# keeboartouch.net
KiCad netlist of a schematic drawn in EAGLE
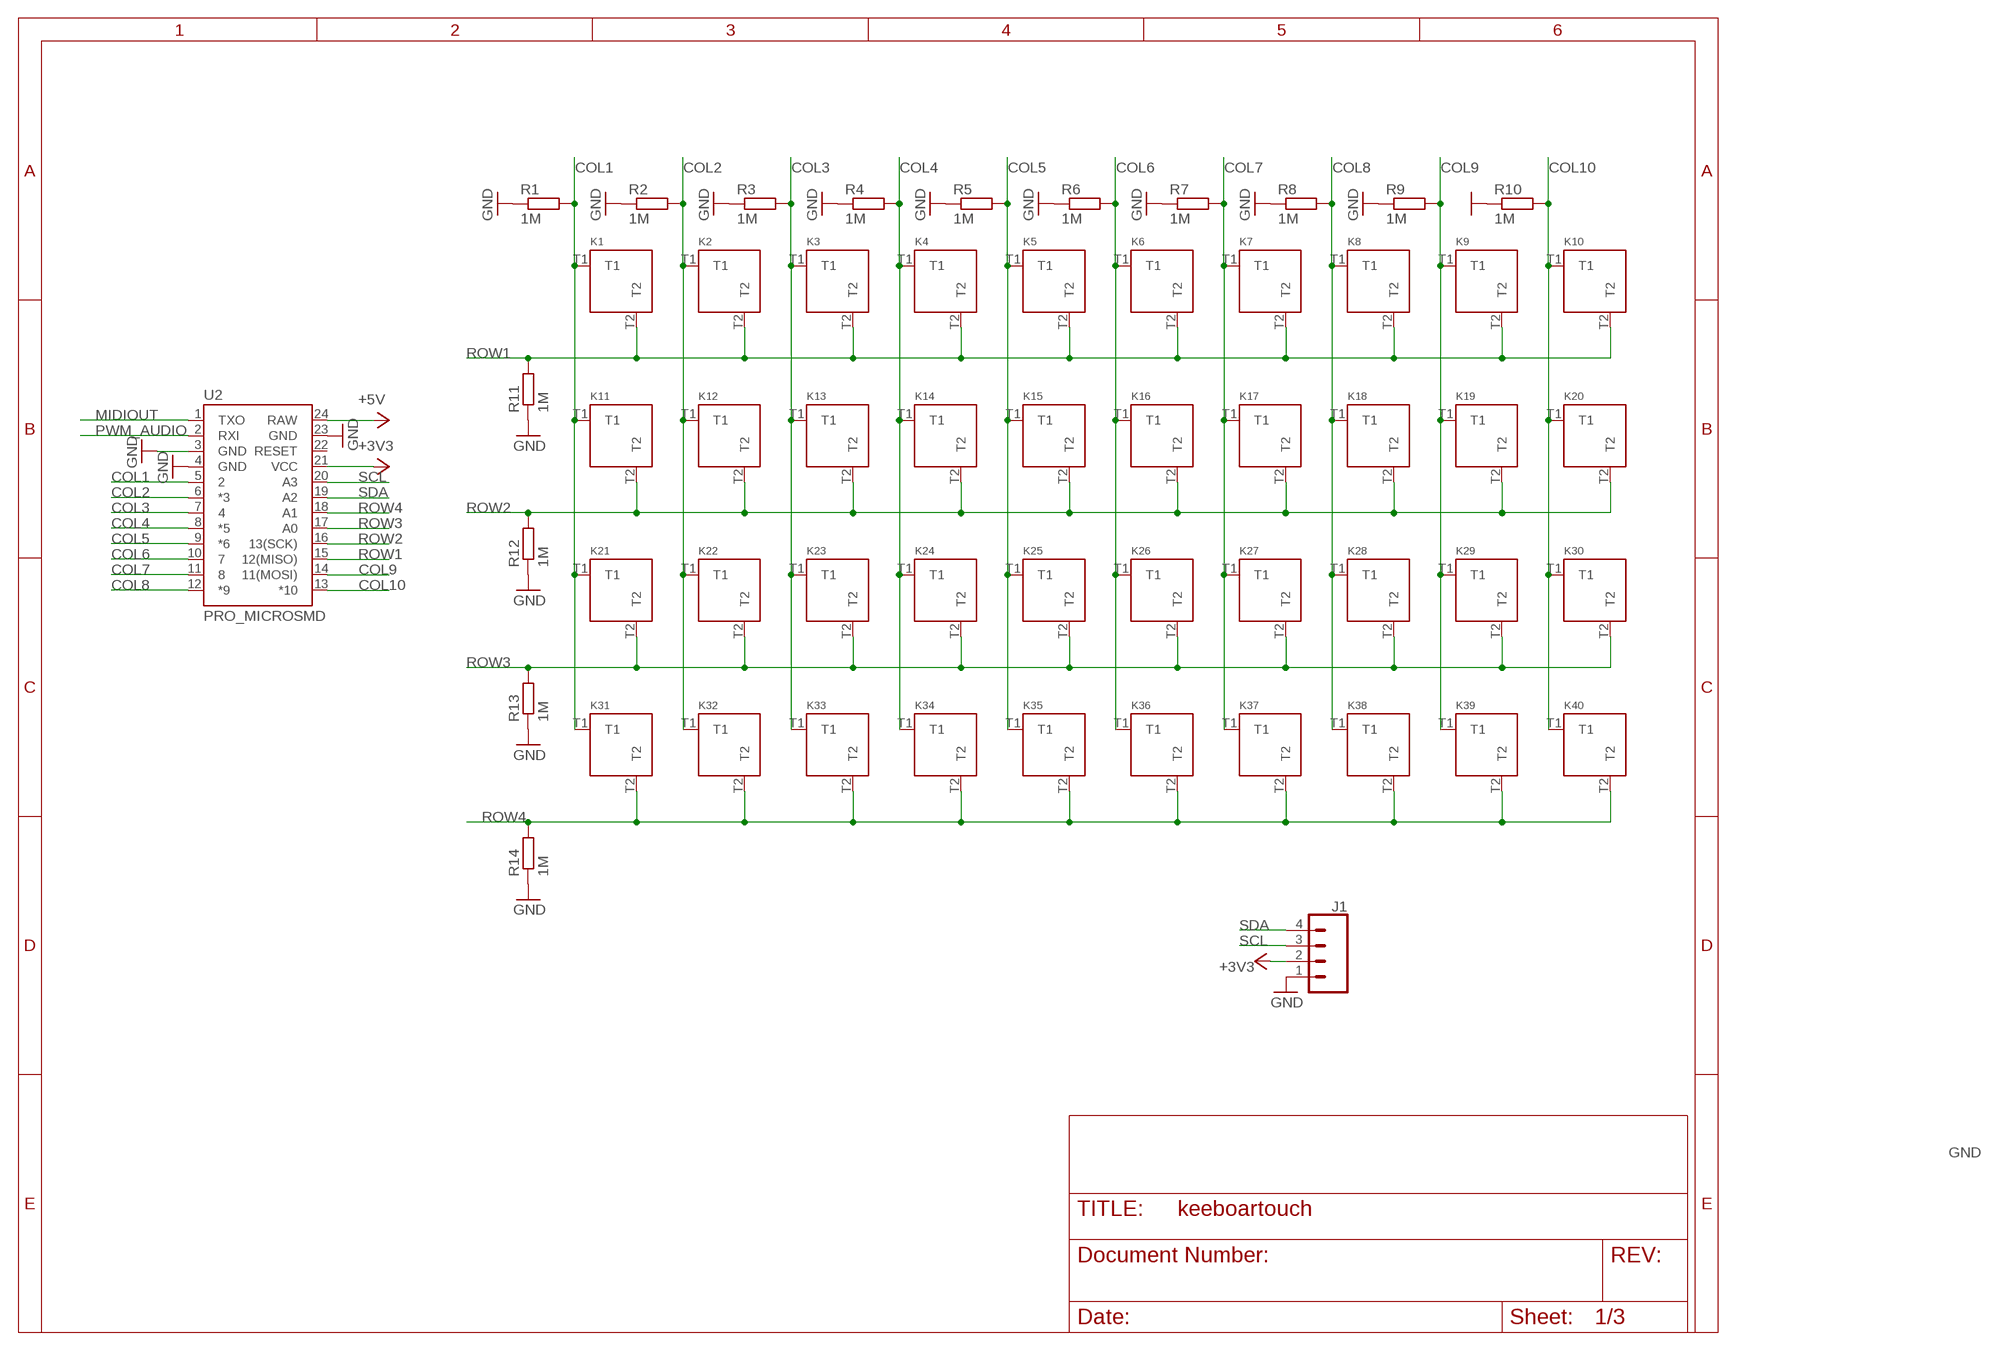
[diagram p0: schematic, sheet 1]

(export (version "E")
  (design (tool "Eeschema 10.0.6"))
  (components
    (comp (ref "J1")
      (value "CONN_04")
      (footprint "eagle-import:1X04")
      (libsource (lib "eagle-import") (part "CONN_04"))
    )
    (comp (ref "K1")
      (value "TOUCHKEY")
      (footprint "eagle-import:TOUCHPAD_KEY_0.5IN")
      (libsource (lib "eagle-import") (part "TOUCHKEY"))
    )
    (comp (ref "K2")
      (value "TOUCHKEY")
      (footprint "eagle-import:TOUCHPAD_KEY_0.5IN")
      (libsource (lib "eagle-import") (part "TOUCHKEY"))
    )
    (comp (ref "K3")
      (value "TOUCHKEY")
      (footprint "eagle-import:TOUCHPAD_KEY_0.5IN")
      (libsource (lib "eagle-import") (part "TOUCHKEY"))
    )
    (comp (ref "K4")
      (value "TOUCHKEY")
      (footprint "eagle-import:TOUCHPAD_KEY_0.5IN")
      (libsource (lib "eagle-import") (part "TOUCHKEY"))
    )
    (comp (ref "K5")
      (value "TOUCHKEY")
      (footprint "eagle-import:TOUCHPAD_KEY_0.5IN")
      (libsource (lib "eagle-import") (part "TOUCHKEY"))
    )
    (comp (ref "K6")
      (value "TOUCHKEY")
      (footprint "eagle-import:TOUCHPAD_KEY_0.5IN")
      (libsource (lib "eagle-import") (part "TOUCHKEY"))
    )
    (comp (ref "K7")
      (value "TOUCHKEY")
      (footprint "eagle-import:TOUCHPAD_KEY_0.5IN")
      (libsource (lib "eagle-import") (part "TOUCHKEY"))
    )
    (comp (ref "K8")
      (value "TOUCHKEY")
      (footprint "eagle-import:TOUCHPAD_KEY_0.5IN")
      (libsource (lib "eagle-import") (part "TOUCHKEY"))
    )
    (comp (ref "K9")
      (value "TOUCHKEY")
      (footprint "eagle-import:TOUCHPAD_KEY_0.5IN")
      (libsource (lib "eagle-import") (part "TOUCHKEY"))
    )
    (comp (ref "K10")
      (value "TOUCHKEY")
      (footprint "eagle-import:TOUCHPAD_KEY_0.5IN")
      (libsource (lib "eagle-import") (part "TOUCHKEY"))
    )
    (comp (ref "K11")
      (value "TOUCHKEY")
      (footprint "eagle-import:TOUCHPAD_KEY_0.5IN")
      (libsource (lib "eagle-import") (part "TOUCHKEY"))
    )
    (comp (ref "K12")
      (value "TOUCHKEY")
      (footprint "eagle-import:TOUCHPAD_KEY_0.5IN")
      (libsource (lib "eagle-import") (part "TOUCHKEY"))
    )
    (comp (ref "K13")
      (value "TOUCHKEY")
      (footprint "eagle-import:TOUCHPAD_KEY_0.5IN")
      (libsource (lib "eagle-import") (part "TOUCHKEY"))
    )
    (comp (ref "K14")
      (value "TOUCHKEY")
      (footprint "eagle-import:TOUCHPAD_KEY_0.5IN")
      (libsource (lib "eagle-import") (part "TOUCHKEY"))
    )
    (comp (ref "K15")
      (value "TOUCHKEY")
      (footprint "eagle-import:TOUCHPAD_KEY_0.5IN")
      (libsource (lib "eagle-import") (part "TOUCHKEY"))
    )
    (comp (ref "K16")
      (value "TOUCHKEY")
      (footprint "eagle-import:TOUCHPAD_KEY_0.5IN")
      (libsource (lib "eagle-import") (part "TOUCHKEY"))
    )
    (comp (ref "K17")
      (value "TOUCHKEY")
      (footprint "eagle-import:TOUCHPAD_KEY_0.5IN")
      (libsource (lib "eagle-import") (part "TOUCHKEY"))
    )
    (comp (ref "K18")
      (value "TOUCHKEY")
      (footprint "eagle-import:TOUCHPAD_KEY_0.5IN")
      (libsource (lib "eagle-import") (part "TOUCHKEY"))
    )
    (comp (ref "K19")
      (value "TOUCHKEY")
      (footprint "eagle-import:TOUCHPAD_KEY_0.5IN")
      (libsource (lib "eagle-import") (part "TOUCHKEY"))
    )
    (comp (ref "K20")
      (value "TOUCHKEY")
      (footprint "eagle-import:TOUCHPAD_KEY_0.5IN")
      (libsource (lib "eagle-import") (part "TOUCHKEY"))
    )
    (comp (ref "K21")
      (value "TOUCHKEY")
      (footprint "eagle-import:TOUCHPAD_KEY_0.5IN")
      (libsource (lib "eagle-import") (part "TOUCHKEY"))
    )
    (comp (ref "K22")
      (value "TOUCHKEY")
      (footprint "eagle-import:TOUCHPAD_KEY_0.5IN")
      (libsource (lib "eagle-import") (part "TOUCHKEY"))
    )
    (comp (ref "K23")
      (value "TOUCHKEY")
      (footprint "eagle-import:TOUCHPAD_KEY_0.5IN")
      (libsource (lib "eagle-import") (part "TOUCHKEY"))
    )
    (comp (ref "K24")
      (value "TOUCHKEY")
      (footprint "eagle-import:TOUCHPAD_KEY_0.5IN")
      (libsource (lib "eagle-import") (part "TOUCHKEY"))
    )
    (comp (ref "K25")
      (value "TOUCHKEY")
      (footprint "eagle-import:TOUCHPAD_KEY_0.5IN")
      (libsource (lib "eagle-import") (part "TOUCHKEY"))
    )
    (comp (ref "K26")
      (value "TOUCHKEY")
      (footprint "eagle-import:TOUCHPAD_KEY_0.5IN")
      (libsource (lib "eagle-import") (part "TOUCHKEY"))
    )
    (comp (ref "K27")
      (value "TOUCHKEY")
      (footprint "eagle-import:TOUCHPAD_KEY_0.5IN")
      (libsource (lib "eagle-import") (part "TOUCHKEY"))
    )
    (comp (ref "K28")
      (value "TOUCHKEY")
      (footprint "eagle-import:TOUCHPAD_KEY_0.5IN")
      (libsource (lib "eagle-import") (part "TOUCHKEY"))
    )
    (comp (ref "K29")
      (value "TOUCHKEY")
      (footprint "eagle-import:TOUCHPAD_KEY_0.5IN")
      (libsource (lib "eagle-import") (part "TOUCHKEY"))
    )
    (comp (ref "K30")
      (value "TOUCHKEY")
      (footprint "eagle-import:TOUCHPAD_KEY_0.5IN")
      (libsource (lib "eagle-import") (part "TOUCHKEY"))
    )
    (comp (ref "K31")
      (value "TOUCHKEY")
      (footprint "eagle-import:TOUCHPAD_KEY_0.5IN")
      (libsource (lib "eagle-import") (part "TOUCHKEY"))
    )
    (comp (ref "K32")
      (value "TOUCHKEY")
      (footprint "eagle-import:TOUCHPAD_KEY_0.5IN")
      (libsource (lib "eagle-import") (part "TOUCHKEY"))
    )
    (comp (ref "K33")
      (value "TOUCHKEY")
      (footprint "eagle-import:TOUCHPAD_KEY_0.5IN")
      (libsource (lib "eagle-import") (part "TOUCHKEY"))
    )
    (comp (ref "K34")
      (value "TOUCHKEY")
      (footprint "eagle-import:TOUCHPAD_KEY_0.5IN")
      (libsource (lib "eagle-import") (part "TOUCHKEY"))
    )
    (comp (ref "K35")
      (value "TOUCHKEY")
      (footprint "eagle-import:TOUCHPAD_KEY_0.5IN")
      (libsource (lib "eagle-import") (part "TOUCHKEY"))
    )
    (comp (ref "K36")
      (value "TOUCHKEY")
      (footprint "eagle-import:TOUCHPAD_KEY_0.5IN")
      (libsource (lib "eagle-import") (part "TOUCHKEY"))
    )
    (comp (ref "K37")
      (value "TOUCHKEY")
      (footprint "eagle-import:TOUCHPAD_KEY_0.5IN")
      (libsource (lib "eagle-import") (part "TOUCHKEY"))
    )
    (comp (ref "K38")
      (value "TOUCHKEY")
      (footprint "eagle-import:TOUCHPAD_KEY_0.5IN")
      (libsource (lib "eagle-import") (part "TOUCHKEY"))
    )
    (comp (ref "K39")
      (value "TOUCHKEY")
      (footprint "eagle-import:TOUCHPAD_KEY_0.5IN")
      (libsource (lib "eagle-import") (part "TOUCHKEY"))
    )
    (comp (ref "K40")
      (value "TOUCHKEY")
      (footprint "eagle-import:TOUCHPAD_KEY_0.5IN")
      (libsource (lib "eagle-import") (part "TOUCHKEY"))
    )
    (comp (ref "R1")
      (value "1M")
      (footprint "eagle-import:R0805")
      (libsource (lib "eagle-import") (part "R-EU_R0805"))
    )
    (comp (ref "R2")
      (value "1M")
      (footprint "eagle-import:R0805")
      (libsource (lib "eagle-import") (part "R-EU_R0805"))
    )
    (comp (ref "R3")
      (value "1M")
      (footprint "eagle-import:R0805")
      (libsource (lib "eagle-import") (part "R-EU_R0805"))
    )
    (comp (ref "R4")
      (value "1M")
      (footprint "eagle-import:R0805")
      (libsource (lib "eagle-import") (part "R-EU_R0805"))
    )
    (comp (ref "R5")
      (value "1M")
      (footprint "eagle-import:R0805")
      (libsource (lib "eagle-import") (part "R-EU_R0805"))
    )
    (comp (ref "R6")
      (value "1M")
      (footprint "eagle-import:R0805")
      (libsource (lib "eagle-import") (part "R-EU_R0805"))
    )
    (comp (ref "R7")
      (value "1M")
      (footprint "eagle-import:R0805")
      (libsource (lib "eagle-import") (part "R-EU_R0805"))
    )
    (comp (ref "R8")
      (value "1M")
      (footprint "eagle-import:R0805")
      (libsource (lib "eagle-import") (part "R-EU_R0805"))
    )
    (comp (ref "R9")
      (value "1M")
      (footprint "eagle-import:R0805")
      (libsource (lib "eagle-import") (part "R-EU_R0805"))
    )
    (comp (ref "R10")
      (value "1M")
      (footprint "eagle-import:R0805")
      (libsource (lib "eagle-import") (part "R-EU_R0805"))
    )
    (comp (ref "R11")
      (value "1M")
      (footprint "eagle-import:R0805")
      (libsource (lib "eagle-import") (part "R-EU_R0805"))
    )
    (comp (ref "R12")
      (value "1M")
      (footprint "eagle-import:R0805")
      (libsource (lib "eagle-import") (part "R-EU_R0805"))
    )
    (comp (ref "R13")
      (value "1M")
      (footprint "eagle-import:R0805")
      (libsource (lib "eagle-import") (part "R-EU_R0805"))
    )
    (comp (ref "R14")
      (value "1M")
      (footprint "eagle-import:R0805")
      (libsource (lib "eagle-import") (part "R-EU_R0805"))
    )
    (comp (ref "U2")
      (value "PRO_MICROSMD")
      (footprint "eagle-import:PRO_MICRO_SMD")
      (libsource (lib "eagle-import") (part "PRO_MICROSMD"))
    )
  )
  (nets
    (net (code "1") (name "+3V3") (class "Default")
      (node (ref "J1") (pin "2") (pinfunction "2_2") (pintype "passive"))
      (node (ref "U2") (pin "21") (pinfunction "VCC_21") (pintype "power_in"))
    )
    (net (code "2") (name "+5V") (class "Default")
      (node (ref "U2") (pin "24") (pinfunction "RAW_24") (pintype "power_in"))
    )
    (net (code "3") (name "COL1") (class "Default")
      (node (ref "K1") (pin "T1") (pinfunction "T1_T1") (pintype "bidirectional"))
      (node (ref "K11") (pin "T1") (pinfunction "T1_T1") (pintype "bidirectional"))
      (node (ref "K21") (pin "T1") (pinfunction "T1_T1") (pintype "bidirectional"))
      (node (ref "K31") (pin "T1") (pinfunction "T1_T1") (pintype "bidirectional"))
      (node (ref "R1") (pin "2") (pinfunction "2_2") (pintype "passive"))
      (node (ref "U2") (pin "5") (pinfunction "2_5") (pintype "bidirectional"))
    )
    (net (code "4") (name "COL2") (class "Default")
      (node (ref "K12") (pin "T1") (pinfunction "T1_T1") (pintype "bidirectional"))
      (node (ref "K2") (pin "T1") (pinfunction "T1_T1") (pintype "bidirectional"))
      (node (ref "K22") (pin "T1") (pinfunction "T1_T1") (pintype "bidirectional"))
      (node (ref "K32") (pin "T1") (pinfunction "T1_T1") (pintype "bidirectional"))
      (node (ref "R2") (pin "2") (pinfunction "2_2") (pintype "passive"))
      (node (ref "U2") (pin "6") (pinfunction "*3_6") (pintype "bidirectional"))
    )
    (net (code "5") (name "COL3") (class "Default")
      (node (ref "K13") (pin "T1") (pinfunction "T1_T1") (pintype "bidirectional"))
      (node (ref "K23") (pin "T1") (pinfunction "T1_T1") (pintype "bidirectional"))
      (node (ref "K3") (pin "T1") (pinfunction "T1_T1") (pintype "bidirectional"))
      (node (ref "K33") (pin "T1") (pinfunction "T1_T1") (pintype "bidirectional"))
      (node (ref "R3") (pin "2") (pinfunction "2_2") (pintype "passive"))
      (node (ref "U2") (pin "7") (pinfunction "4_7") (pintype "bidirectional"))
    )
    (net (code "6") (name "COL4") (class "Default")
      (node (ref "K14") (pin "T1") (pinfunction "T1_T1") (pintype "bidirectional"))
      (node (ref "K24") (pin "T1") (pinfunction "T1_T1") (pintype "bidirectional"))
      (node (ref "K34") (pin "T1") (pinfunction "T1_T1") (pintype "bidirectional"))
      (node (ref "K4") (pin "T1") (pinfunction "T1_T1") (pintype "bidirectional"))
      (node (ref "R4") (pin "2") (pinfunction "2_2") (pintype "passive"))
      (node (ref "U2") (pin "8") (pinfunction "*5_8") (pintype "bidirectional"))
    )
    (net (code "7") (name "COL5") (class "Default")
      (node (ref "K15") (pin "T1") (pinfunction "T1_T1") (pintype "bidirectional"))
      (node (ref "K25") (pin "T1") (pinfunction "T1_T1") (pintype "bidirectional"))
      (node (ref "K35") (pin "T1") (pinfunction "T1_T1") (pintype "bidirectional"))
      (node (ref "K5") (pin "T1") (pinfunction "T1_T1") (pintype "bidirectional"))
      (node (ref "R5") (pin "2") (pinfunction "2_2") (pintype "passive"))
      (node (ref "U2") (pin "9") (pinfunction "*6_9") (pintype "bidirectional"))
    )
    (net (code "8") (name "COL6") (class "Default")
      (node (ref "K16") (pin "T1") (pinfunction "T1_T1") (pintype "bidirectional"))
      (node (ref "K26") (pin "T1") (pinfunction "T1_T1") (pintype "bidirectional"))
      (node (ref "K36") (pin "T1") (pinfunction "T1_T1") (pintype "bidirectional"))
      (node (ref "K6") (pin "T1") (pinfunction "T1_T1") (pintype "bidirectional"))
      (node (ref "R6") (pin "2") (pinfunction "2_2") (pintype "passive"))
      (node (ref "U2") (pin "10") (pinfunction "7_10") (pintype "bidirectional"))
    )
    (net (code "9") (name "COL7") (class "Default")
      (node (ref "K17") (pin "T1") (pinfunction "T1_T1") (pintype "bidirectional"))
      (node (ref "K27") (pin "T1") (pinfunction "T1_T1") (pintype "bidirectional"))
      (node (ref "K37") (pin "T1") (pinfunction "T1_T1") (pintype "bidirectional"))
      (node (ref "K7") (pin "T1") (pinfunction "T1_T1") (pintype "bidirectional"))
      (node (ref "R7") (pin "2") (pinfunction "2_2") (pintype "passive"))
      (node (ref "U2") (pin "11") (pinfunction "8_11") (pintype "bidirectional"))
    )
    (net (code "10") (name "COL8") (class "Default")
      (node (ref "K18") (pin "T1") (pinfunction "T1_T1") (pintype "bidirectional"))
      (node (ref "K28") (pin "T1") (pinfunction "T1_T1") (pintype "bidirectional"))
      (node (ref "K38") (pin "T1") (pinfunction "T1_T1") (pintype "bidirectional"))
      (node (ref "K8") (pin "T1") (pinfunction "T1_T1") (pintype "bidirectional"))
      (node (ref "R8") (pin "2") (pinfunction "2_2") (pintype "passive"))
      (node (ref "U2") (pin "12") (pinfunction "*9_12") (pintype "bidirectional"))
    )
    (net (code "11") (name "COL9") (class "Default")
      (node (ref "K19") (pin "T1") (pinfunction "T1_T1") (pintype "bidirectional"))
      (node (ref "K29") (pin "T1") (pinfunction "T1_T1") (pintype "bidirectional"))
      (node (ref "K39") (pin "T1") (pinfunction "T1_T1") (pintype "bidirectional"))
      (node (ref "K9") (pin "T1") (pinfunction "T1_T1") (pintype "bidirectional"))
      (node (ref "R9") (pin "2") (pinfunction "2_2") (pintype "passive"))
      (node (ref "U2") (pin "14") (pinfunction "11(MOSI)_14") (pintype "bidirectional"))
    )
    (net (code "12") (name "COL10") (class "Default")
      (node (ref "K10") (pin "T1") (pinfunction "T1_T1") (pintype "bidirectional"))
      (node (ref "K20") (pin "T1") (pinfunction "T1_T1") (pintype "bidirectional"))
      (node (ref "K30") (pin "T1") (pinfunction "T1_T1") (pintype "bidirectional"))
      (node (ref "K40") (pin "T1") (pinfunction "T1_T1") (pintype "bidirectional"))
      (node (ref "R10") (pin "2") (pinfunction "2_2") (pintype "passive"))
      (node (ref "U2") (pin "13") (pinfunction "*10_13") (pintype "bidirectional"))
    )
    (net (code "13") (name "GND") (class "Default")
      (node (ref "J1") (pin "1") (pinfunction "1_1") (pintype "passive"))
      (node (ref "R1") (pin "1") (pinfunction "1_1") (pintype "passive"))
      (node (ref "R10") (pin "1") (pinfunction "1_1") (pintype "passive"))
      (node (ref "R11") (pin "1") (pinfunction "1_1") (pintype "passive"))
      (node (ref "R12") (pin "1") (pinfunction "1_1") (pintype "passive"))
      (node (ref "R13") (pin "1") (pinfunction "1_1") (pintype "passive"))
      (node (ref "R14") (pin "1") (pinfunction "1_1") (pintype "passive"))
      (node (ref "R2") (pin "1") (pinfunction "1_1") (pintype "passive"))
      (node (ref "R3") (pin "1") (pinfunction "1_1") (pintype "passive"))
      (node (ref "R4") (pin "1") (pinfunction "1_1") (pintype "passive"))
      (node (ref "R5") (pin "1") (pinfunction "1_1") (pintype "passive"))
      (node (ref "R6") (pin "1") (pinfunction "1_1") (pintype "passive"))
      (node (ref "R7") (pin "1") (pinfunction "1_1") (pintype "passive"))
      (node (ref "R8") (pin "1") (pinfunction "1_1") (pintype "passive"))
      (node (ref "R9") (pin "1") (pinfunction "1_1") (pintype "passive"))
      (node (ref "U2") (pin "23") (pinfunction "GND_23") (pintype "power_in"))
      (node (ref "U2") (pin "3") (pinfunction "GND_3") (pintype "power_in"))
      (node (ref "U2") (pin "4") (pinfunction "GND_4") (pintype "power_in"))
    )
    (net (code "14") (name "MIDIOUT") (class "Default")
      (node (ref "U2") (pin "1") (pinfunction "TXO_1") (pintype "bidirectional"))
    )
    (net (code "15") (name "PWM_AUDIO") (class "Default")
      (node (ref "U2") (pin "2") (pinfunction "RXI_2") (pintype "bidirectional"))
    )
    (net (code "16") (name "ROW1") (class "Default")
      (node (ref "K1") (pin "T2") (pinfunction "T2_T2") (pintype "bidirectional"))
      (node (ref "K10") (pin "T2") (pinfunction "T2_T2") (pintype "bidirectional"))
      (node (ref "K2") (pin "T2") (pinfunction "T2_T2") (pintype "bidirectional"))
      (node (ref "K3") (pin "T2") (pinfunction "T2_T2") (pintype "bidirectional"))
      (node (ref "K4") (pin "T2") (pinfunction "T2_T2") (pintype "bidirectional"))
      (node (ref "K5") (pin "T2") (pinfunction "T2_T2") (pintype "bidirectional"))
      (node (ref "K6") (pin "T2") (pinfunction "T2_T2") (pintype "bidirectional"))
      (node (ref "K7") (pin "T2") (pinfunction "T2_T2") (pintype "bidirectional"))
      (node (ref "K8") (pin "T2") (pinfunction "T2_T2") (pintype "bidirectional"))
      (node (ref "K9") (pin "T2") (pinfunction "T2_T2") (pintype "bidirectional"))
      (node (ref "R11") (pin "2") (pinfunction "2_2") (pintype "passive"))
      (node (ref "U2") (pin "15") (pinfunction "12(MISO)_15") (pintype "bidirectional"))
    )
    (net (code "17") (name "ROW2") (class "Default")
      (node (ref "K11") (pin "T2") (pinfunction "T2_T2") (pintype "bidirectional"))
      (node (ref "K12") (pin "T2") (pinfunction "T2_T2") (pintype "bidirectional"))
      (node (ref "K13") (pin "T2") (pinfunction "T2_T2") (pintype "bidirectional"))
      (node (ref "K14") (pin "T2") (pinfunction "T2_T2") (pintype "bidirectional"))
      (node (ref "K15") (pin "T2") (pinfunction "T2_T2") (pintype "bidirectional"))
      (node (ref "K16") (pin "T2") (pinfunction "T2_T2") (pintype "bidirectional"))
      (node (ref "K17") (pin "T2") (pinfunction "T2_T2") (pintype "bidirectional"))
      (node (ref "K18") (pin "T2") (pinfunction "T2_T2") (pintype "bidirectional"))
      (node (ref "K19") (pin "T2") (pinfunction "T2_T2") (pintype "bidirectional"))
      (node (ref "K20") (pin "T2") (pinfunction "T2_T2") (pintype "bidirectional"))
      (node (ref "R12") (pin "2") (pinfunction "2_2") (pintype "passive"))
      (node (ref "U2") (pin "16") (pinfunction "13(SCK)_16") (pintype "bidirectional"))
    )
    (net (code "18") (name "ROW3") (class "Default")
      (node (ref "K21") (pin "T2") (pinfunction "T2_T2") (pintype "bidirectional"))
      (node (ref "K22") (pin "T2") (pinfunction "T2_T2") (pintype "bidirectional"))
      (node (ref "K23") (pin "T2") (pinfunction "T2_T2") (pintype "bidirectional"))
      (node (ref "K24") (pin "T2") (pinfunction "T2_T2") (pintype "bidirectional"))
      (node (ref "K25") (pin "T2") (pinfunction "T2_T2") (pintype "bidirectional"))
      (node (ref "K26") (pin "T2") (pinfunction "T2_T2") (pintype "bidirectional"))
      (node (ref "K27") (pin "T2") (pinfunction "T2_T2") (pintype "bidirectional"))
      (node (ref "K28") (pin "T2") (pinfunction "T2_T2") (pintype "bidirectional"))
      (node (ref "K29") (pin "T2") (pinfunction "T2_T2") (pintype "bidirectional"))
      (node (ref "K30") (pin "T2") (pinfunction "T2_T2") (pintype "bidirectional"))
      (node (ref "R13") (pin "2") (pinfunction "2_2") (pintype "passive"))
      (node (ref "U2") (pin "17") (pinfunction "A0_17") (pintype "bidirectional"))
    )
    (net (code "19") (name "ROW4") (class "Default")
      (node (ref "K31") (pin "T2") (pinfunction "T2_T2") (pintype "bidirectional"))
      (node (ref "K32") (pin "T2") (pinfunction "T2_T2") (pintype "bidirectional"))
      (node (ref "K33") (pin "T2") (pinfunction "T2_T2") (pintype "bidirectional"))
      (node (ref "K34") (pin "T2") (pinfunction "T2_T2") (pintype "bidirectional"))
      (node (ref "K35") (pin "T2") (pinfunction "T2_T2") (pintype "bidirectional"))
      (node (ref "K36") (pin "T2") (pinfunction "T2_T2") (pintype "bidirectional"))
      (node (ref "K37") (pin "T2") (pinfunction "T2_T2") (pintype "bidirectional"))
      (node (ref "K38") (pin "T2") (pinfunction "T2_T2") (pintype "bidirectional"))
      (node (ref "K39") (pin "T2") (pinfunction "T2_T2") (pintype "bidirectional"))
      (node (ref "K40") (pin "T2") (pinfunction "T2_T2") (pintype "bidirectional"))
      (node (ref "R14") (pin "2") (pinfunction "2_2") (pintype "passive"))
      (node (ref "U2") (pin "18") (pinfunction "A1_18") (pintype "bidirectional"))
    )
    (net (code "20") (name "SCL") (class "Default")
      (node (ref "J1") (pin "3") (pinfunction "3_3") (pintype "passive"))
      (node (ref "U2") (pin "20") (pinfunction "A3_20") (pintype "bidirectional"))
    )
    (net (code "21") (name "SDA") (class "Default")
      (node (ref "J1") (pin "4") (pinfunction "4_4") (pintype "passive"))
      (node (ref "U2") (pin "19") (pinfunction "A2_19") (pintype "bidirectional"))
    )
    (net (code "22") (name "unconnected-(U2-RESET-Pad22)") (class "Default")
      (node (ref "U2") (pin "22") (pinfunction "RESET_22") (pintype "bidirectional"))
    )
  )
)
